# 4_-MCU_POWER.net
KiCad netlist of a schematic drawn in Altium Designer
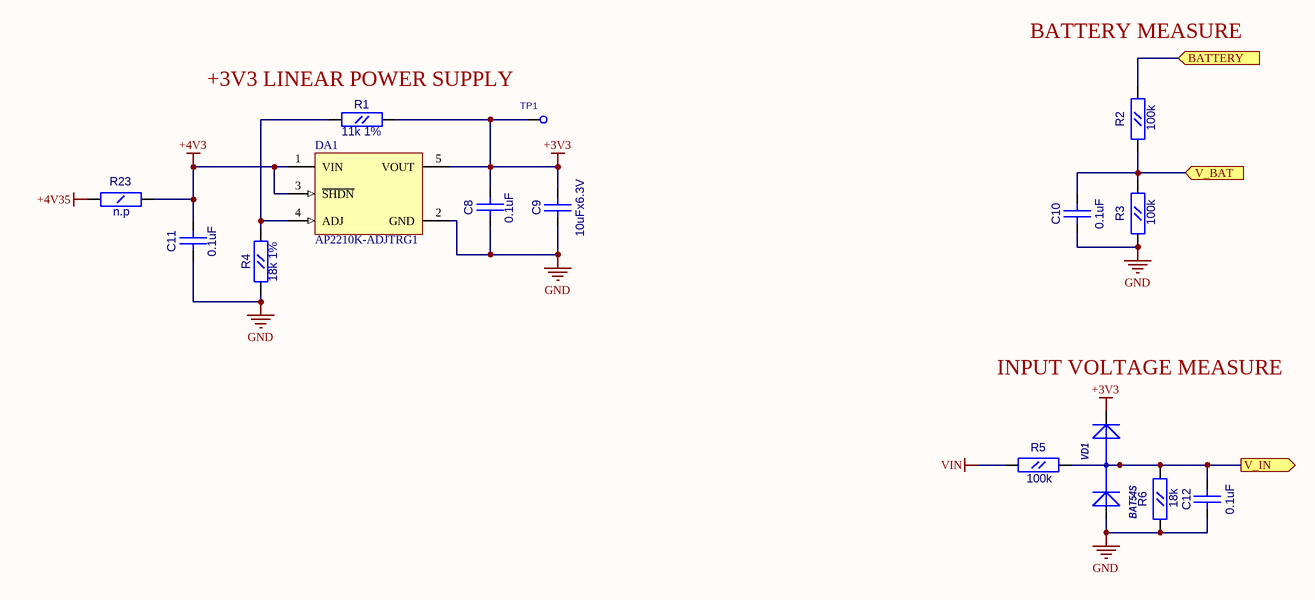
[diagram p0: [4]-MCU_POWER.SchDoc]

(export (version "E")
  (design (tool "Eeschema 10.0.6"))
  (components
    (comp (ref "C8")
      (value "0.1uF")
      (footprint "CC0603")
      (description "CC0603")
      (libsource (lib "gprs_modem_2") (part "CC0603"))
    )
    (comp (ref "C9")
      (value "10uFx6.3V")
      (footprint "CC0805")
      (description "CC0805")
      (libsource (lib "gprs_modem_2") (part "CC0805"))
    )
    (comp (ref "C10")
      (value "0.1uF")
      (footprint "CC0603")
      (description "CC0603")
      (libsource (lib "gprs_modem_2") (part "CC0603"))
    )
    (comp (ref "C11")
      (value "0.1uF")
      (footprint "CC0603")
      (description "CC0603")
      (libsource (lib "gprs_modem_2") (part "CC0603"))
    )
    (comp (ref "C12")
      (value "0.1uF")
      (footprint "CC0603")
      (description "CC0603")
      (libsource (lib "gprs_modem_2") (part "CC0603"))
    )
    (comp (ref "DA1")
      (value "AP2210K-ADJTRG1")
      (footprint "SOT23-5")
      (fields (field (name "PUBLISHER") "Altium Limited"))
      (libsource (lib "gprs_modem_2") (part "MCP1824T-ADJE/OT"))
    )
    (comp (ref "R1")
      (value "11k 1%")
      (footprint "RC0603")
      (description "RC0603")
      (libsource (lib "gprs_modem_2") (part "RC0603"))
    )
    (comp (ref "R2")
      (value "100k")
      (footprint "RC0603")
      (description "RC0603")
      (libsource (lib "gprs_modem_2") (part "RC0603"))
    )
    (comp (ref "R3")
      (value "100k")
      (footprint "RC0603")
      (description "RC0603")
      (libsource (lib "gprs_modem_2") (part "RC0603"))
    )
    (comp (ref "R4")
      (value "18k 1%")
      (footprint "RC0603")
      (description "RC0603")
      (libsource (lib "gprs_modem_2") (part "RC0603"))
    )
    (comp (ref "R5")
      (value "100k")
      (footprint "RC0603")
      (description "RC0603")
      (libsource (lib "gprs_modem_2") (part "RC0603"))
    )
    (comp (ref "R6")
      (value "18k")
      (footprint "RC0603")
      (description "RC0603")
      (libsource (lib "gprs_modem_2") (part "RC0603"))
    )
    (comp (ref "R23")
      (value "n.p")
      (footprint "RC1206")
      (description "RC1206")
      (libsource (lib "fizik_lib") (part "RC1206"))
    )
    (comp (ref "TP1")
      (value "TESTPOINT1")
      (footprint "TESTPOINT1")
      (libsource (lib "fizik_lib") (part "TESTPOINT1"))
    )
    (comp (ref "VD1")
      (value "BAT54S")
      (footprint "SOT-23(GSD)")
      (description "1.0 Ampere General Purpose Rectifier")
      (libsource (lib "gprs_modem_2") (part "BAT54S"))
    )
  )
  (nets
    (net (code "1") (name "+3V3") (class "Default")
      (node (ref "C8") (pin "1") (pinfunction "A_1") (pintype "passive"))
      (node (ref "C9") (pin "2") (pinfunction "B_2") (pintype "passive"))
      (node (ref "DA1") (pin "5") (pinfunction "VOUT_5") (pintype "power_in"))
      (node (ref "R1") (pin "2") (pinfunction "B_2") (pintype "passive"))
      (node (ref "TP1") (pin "1") (pintype "passive"))
      (node (ref "VD1") (pin "2") (pinfunction "K_2") (pintype "passive"))
    )
    (net (code "2") (name "+4V3") (class "Default")
      (node (ref "C11") (pin "1") (pinfunction "A_1") (pintype "passive"))
      (node (ref "DA1") (pin "1") (pinfunction "VIN_1") (pintype "power_in"))
      (node (ref "DA1") (pin "3") (pinfunction "~{SHDN}_3") (pintype "input"))
      (node (ref "R23") (pin "2") (pinfunction "B_2") (pintype "passive"))
    )
    (net (code "3") (name "+4V35") (class "Default")
      (node (ref "R23") (pin "1") (pinfunction "A_1") (pintype "passive"))
    )
    (net (code "4") (name "/BATTERY") (class "Default")
      (node (ref "R2") (pin "2") (pinfunction "B_2") (pintype "passive"))
    )
    (net (code "5") (name "/V_BAT") (class "Default")
      (node (ref "C10") (pin "2") (pinfunction "B_2") (pintype "passive"))
      (node (ref "R2") (pin "1") (pinfunction "A_1") (pintype "passive"))
      (node (ref "R3") (pin "2") (pinfunction "B_2") (pintype "passive"))
    )
    (net (code "6") (name "/V_IN") (class "Default")
      (node (ref "C12") (pin "2") (pinfunction "B_2") (pintype "passive"))
      (node (ref "R5") (pin "2") (pinfunction "B_2") (pintype "passive"))
      (node (ref "R6") (pin "2") (pinfunction "B_2") (pintype "passive"))
      (node (ref "VD1") (pin "3") (pinfunction "AK_3") (pintype "passive"))
    )
    (net (code "7") (name "GND") (class "Default")
      (node (ref "C10") (pin "1") (pinfunction "A_1") (pintype "passive"))
      (node (ref "C11") (pin "2") (pinfunction "B_2") (pintype "passive"))
      (node (ref "C12") (pin "1") (pinfunction "A_1") (pintype "passive"))
      (node (ref "C8") (pin "2") (pinfunction "B_2") (pintype "passive"))
      (node (ref "C9") (pin "1") (pinfunction "A_1") (pintype "passive"))
      (node (ref "DA1") (pin "2") (pinfunction "GND_2") (pintype "power_in"))
      (node (ref "R3") (pin "1") (pinfunction "A_1") (pintype "passive"))
      (node (ref "R4") (pin "1") (pinfunction "A_1") (pintype "passive"))
      (node (ref "R6") (pin "1") (pinfunction "A_1") (pintype "passive"))
      (node (ref "VD1") (pin "1") (pinfunction "A_1") (pintype "passive"))
    )
    (net (code "8") (name "Net-(DA1-ADJ)") (class "Default")
      (node (ref "DA1") (pin "4") (pinfunction "ADJ_4") (pintype "input"))
      (node (ref "R1") (pin "1") (pinfunction "A_1") (pintype "passive"))
      (node (ref "R4") (pin "2") (pinfunction "B_2") (pintype "passive"))
    )
    (net (code "9") (name "VIN") (class "Default")
      (node (ref "R5") (pin "1") (pinfunction "A_1") (pintype "passive"))
    )
  )
)
